# Thunderboard.net
KiCad netlist of a schematic drawn in EAGLE
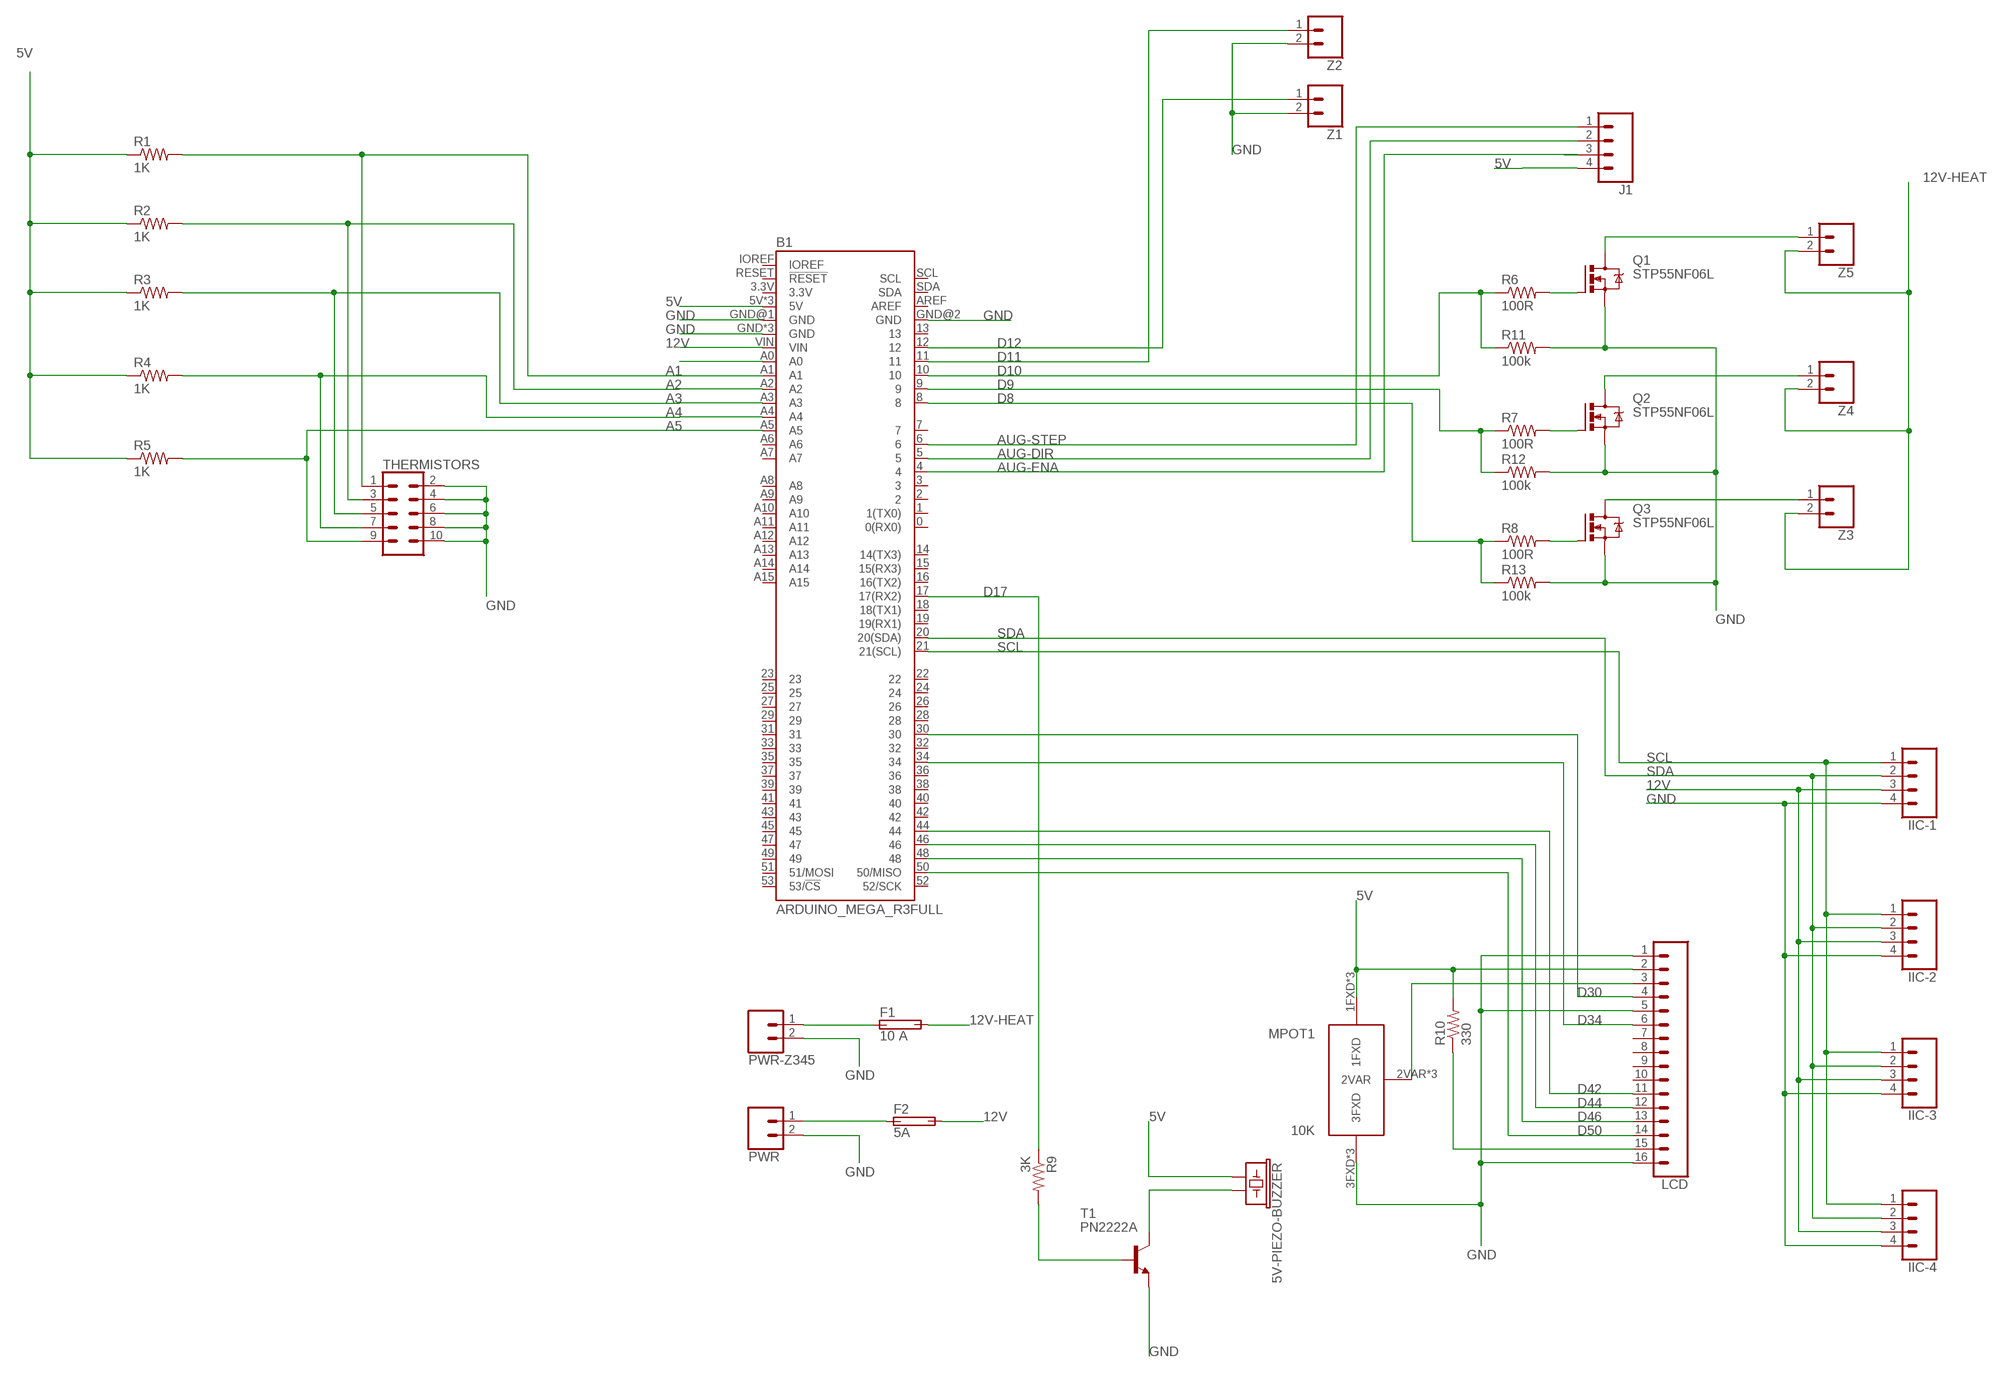
[diagram p0: schematic, sheet 1]

(export (version "E")
  (design (tool "Eeschema 10.0.6"))
  (components
    (comp (ref "5V-PIEZO-BUZZER")
      (value "BUZZER-PTH")
      (footprint "eagle-import:BUZZER-12MM")
      (libsource (lib "eagle-import") (part "BUZZER-PTH"))
    )
    (comp (ref "B1")
      (value "ARDUINO_MEGA_R3FULL")
      (footprint "eagle-import:ARDUINO_MEGA_NO_SILK")
      (libsource (lib "eagle-import") (part "ARDUINO_MEGA_R3FULL"))
    )
    (comp (ref "F1")
      (value "10 A")
      (footprint "eagle-import:MINI-BLADE")
      (libsource (lib "eagle-import") (part "BLADE-FUSE-HOLDER3557-15"))
    )
    (comp (ref "F2")
      (value "5A")
      (footprint "eagle-import:MINI-BLADE")
      (libsource (lib "eagle-import") (part "BLADE-FUSE-HOLDER3557-15"))
    )
    (comp (ref "IIC-1")
      (value "CONN_04")
      (footprint "eagle-import:1X04")
      (libsource (lib "eagle-import") (part "CONN_04"))
    )
    (comp (ref "IIC-2")
      (value "CONN_04")
      (footprint "eagle-import:1X04")
      (libsource (lib "eagle-import") (part "CONN_04"))
    )
    (comp (ref "IIC-3")
      (value "CONN_04")
      (footprint "eagle-import:1X04")
      (libsource (lib "eagle-import") (part "CONN_04"))
    )
    (comp (ref "IIC-4")
      (value "CONN_04")
      (footprint "eagle-import:1X04")
      (libsource (lib "eagle-import") (part "CONN_04"))
    )
    (comp (ref "J1")
      (value "CONN_04")
      (footprint "eagle-import:1X04")
      (libsource (lib "eagle-import") (part "CONN_04"))
    )
    (comp (ref "LCD")
      (value "CONN_16")
      (footprint "eagle-import:1X16")
      (libsource (lib "eagle-import") (part "CONN_16"))
    )
    (comp (ref "MPOT1")
      (value "10K")
      (footprint "eagle-import:POT-MULTI-PACKAGE")
      (libsource (lib "eagle-import") (part "POT-MULTI-PACKAGE"))
    )
    (comp (ref "PWR")
      (value "CONN_023.5MM")
      (footprint "eagle-import:SCREWTERMINAL-3.5MM-2")
      (libsource (lib "eagle-import") (part "CONN_023.5MM"))
    )
    (comp (ref "PWR-Z345")
      (value "CONN_023.5MM")
      (footprint "eagle-import:SCREWTERMINAL-3.5MM-2")
      (libsource (lib "eagle-import") (part "CONN_023.5MM"))
    )
    (comp (ref "Q1")
      (value "STP55NF06L")
      (footprint "eagle-import:TO-220")
      (libsource (lib "eagle-import") (part "STP55NF06L"))
    )
    (comp (ref "Q2")
      (value "STP55NF06L")
      (footprint "eagle-import:TO-220")
      (libsource (lib "eagle-import") (part "STP55NF06L"))
    )
    (comp (ref "Q3")
      (value "STP55NF06L")
      (footprint "eagle-import:TO-220")
      (libsource (lib "eagle-import") (part "STP55NF06L"))
    )
    (comp (ref "R1")
      (value "1K")
      (footprint "eagle-import:0207_7")
      (libsource (lib "eagle-import") (part "R-US_0207/7"))
    )
    (comp (ref "R2")
      (value "1K")
      (footprint "eagle-import:0207_7")
      (libsource (lib "eagle-import") (part "R-US_0207/7"))
    )
    (comp (ref "R3")
      (value "1K")
      (footprint "eagle-import:0207_7")
      (libsource (lib "eagle-import") (part "R-US_0207/7"))
    )
    (comp (ref "R4")
      (value "1K")
      (footprint "eagle-import:0207_7")
      (libsource (lib "eagle-import") (part "R-US_0207/7"))
    )
    (comp (ref "R5")
      (value "1K")
      (footprint "eagle-import:0207_7")
      (libsource (lib "eagle-import") (part "R-US_0207/7"))
    )
    (comp (ref "R6")
      (value "100R")
      (footprint "eagle-import:0207_7")
      (libsource (lib "eagle-import") (part "R-US_0207/7"))
    )
    (comp (ref "R7")
      (value "100R")
      (footprint "eagle-import:0207_7")
      (libsource (lib "eagle-import") (part "R-US_0207/7"))
    )
    (comp (ref "R8")
      (value "100R")
      (footprint "eagle-import:0207_7")
      (libsource (lib "eagle-import") (part "R-US_0207/7"))
    )
    (comp (ref "R9")
      (value "3K")
      (footprint "eagle-import:0207_7")
      (libsource (lib "eagle-import") (part "R-US_0207/7"))
    )
    (comp (ref "R10")
      (value "330")
      (footprint "eagle-import:0207_7")
      (libsource (lib "eagle-import") (part "R-US_0207/7"))
    )
    (comp (ref "R11")
      (value "100k")
      (footprint "eagle-import:0207_7")
      (libsource (lib "eagle-import") (part "R-US_0207/7"))
    )
    (comp (ref "R12")
      (value "100k")
      (footprint "eagle-import:0207_7")
      (libsource (lib "eagle-import") (part "R-US_0207/7"))
    )
    (comp (ref "R13")
      (value "100k")
      (footprint "eagle-import:0207_7")
      (libsource (lib "eagle-import") (part "R-US_0207/7"))
    )
    (comp (ref "T1")
      (value "PN2222A")
      (footprint "eagle-import:TO92-EBC")
      (libsource (lib "eagle-import") (part "-NPN-TO92-EBC"))
    )
    (comp (ref "THERMISTORS")
      (value "CONN_05X2NO_SILK")
      (footprint "eagle-import:2X5_NOSILK")
      (libsource (lib "eagle-import") (part "CONN_05X2NO_SILK"))
    )
    (comp (ref "Z1")
      (value "CONN_02")
      (footprint "eagle-import:1X02")
      (libsource (lib "eagle-import") (part "SparkFun-Connectors_513_CONN_02"))
    )
    (comp (ref "Z2")
      (value "CONN_02")
      (footprint "eagle-import:1X02")
      (libsource (lib "eagle-import") (part "SparkFun-Connectors_513_CONN_02"))
    )
    (comp (ref "Z3")
      (value "CONN_023.5MM")
      (footprint "eagle-import:SCREWTERMINAL-3.5MM-2")
      (libsource (lib "eagle-import") (part "CONN_023.5MM"))
    )
    (comp (ref "Z4")
      (value "CONN_023.5MM")
      (footprint "eagle-import:SCREWTERMINAL-3.5MM-2")
      (libsource (lib "eagle-import") (part "CONN_023.5MM"))
    )
    (comp (ref "Z5")
      (value "CONN_023.5MM")
      (footprint "eagle-import:SCREWTERMINAL-3.5MM-2")
      (libsource (lib "eagle-import") (part "CONN_023.5MM"))
    )
  )
  (nets
    (net (code "1") (name "/5V") (class "Default")
      (node (ref "5V-PIEZO-BUZZER") (pin "+") (pinfunction "1_+") (pintype "passive"))
      (node (ref "B1") (pin "5V") (pinfunction "5V_5V") (pintype "bidirectional"))
      (node (ref "B1") (pin "5V@1") (pinfunction "5V_5V@1") (pintype "bidirectional"))
      (node (ref "B1") (pin "5V@2") (pinfunction "5V_5V@2") (pintype "bidirectional"))
      (node (ref "J1") (pin "4") (pinfunction "4_4") (pintype "passive"))
      (node (ref "LCD") (pin "2") (pinfunction "2_2") (pintype "passive"))
      (node (ref "MPOT1") (pin "1FXD") (pinfunction "1FXD_1FXD") (pintype "bidirectional"))
      (node (ref "MPOT1") (pin "P$7") (pinfunction "1FXD_P$7") (pintype "bidirectional"))
      (node (ref "MPOT1") (pin "P$8") (pinfunction "1FXD_P$8") (pintype "bidirectional"))
      (node (ref "R1") (pin "1") (pinfunction "1_1") (pintype "passive"))
      (node (ref "R10") (pin "2") (pinfunction "2_2") (pintype "passive"))
      (node (ref "R2") (pin "1") (pinfunction "1_1") (pintype "passive"))
      (node (ref "R3") (pin "1") (pinfunction "1_1") (pintype "passive"))
      (node (ref "R4") (pin "1") (pinfunction "1_1") (pintype "passive"))
      (node (ref "R5") (pin "1") (pinfunction "1_1") (pintype "passive"))
    )
    (net (code "2") (name "/12V") (class "Default")
      (node (ref "B1") (pin "VIN") (pinfunction "VIN_VIN") (pintype "bidirectional"))
      (node (ref "F2") (pin "2A") (pinfunction "2_2A") (pintype "passive"))
      (node (ref "F2") (pin "2B") (pinfunction "2_2B") (pintype "passive"))
      (node (ref "IIC-1") (pin "3") (pinfunction "3_3") (pintype "passive"))
      (node (ref "IIC-2") (pin "3") (pinfunction "3_3") (pintype "passive"))
      (node (ref "IIC-3") (pin "3") (pinfunction "3_3") (pintype "passive"))
      (node (ref "IIC-4") (pin "3") (pinfunction "3_3") (pintype "passive"))
    )
    (net (code "3") (name "/12V-HEAT") (class "Default")
      (node (ref "F1") (pin "2A") (pinfunction "2_2A") (pintype "passive"))
      (node (ref "F1") (pin "2B") (pinfunction "2_2B") (pintype "passive"))
      (node (ref "Z3") (pin "2") (pinfunction "2_2") (pintype "passive"))
      (node (ref "Z4") (pin "2") (pinfunction "2_2") (pintype "passive"))
      (node (ref "Z5") (pin "2") (pinfunction "2_2") (pintype "passive"))
    )
    (net (code "4") (name "/A1") (class "Default")
      (node (ref "B1") (pin "A1") (pinfunction "A1_A1") (pintype "bidirectional"))
      (node (ref "R1") (pin "2") (pinfunction "2_2") (pintype "passive"))
      (node (ref "THERMISTORS") (pin "1") (pinfunction "1_1") (pintype "passive"))
    )
    (net (code "5") (name "/A2") (class "Default")
      (node (ref "B1") (pin "A2") (pinfunction "A2_A2") (pintype "bidirectional"))
      (node (ref "R2") (pin "2") (pinfunction "2_2") (pintype "passive"))
      (node (ref "THERMISTORS") (pin "3") (pinfunction "3_3") (pintype "passive"))
    )
    (net (code "6") (name "/A3") (class "Default")
      (node (ref "B1") (pin "A3") (pinfunction "A3_A3") (pintype "bidirectional"))
      (node (ref "R3") (pin "2") (pinfunction "2_2") (pintype "passive"))
      (node (ref "THERMISTORS") (pin "5") (pinfunction "5_5") (pintype "passive"))
    )
    (net (code "7") (name "/A4") (class "Default")
      (node (ref "B1") (pin "A4") (pinfunction "A4_A4") (pintype "bidirectional"))
      (node (ref "R4") (pin "2") (pinfunction "2_2") (pintype "passive"))
      (node (ref "THERMISTORS") (pin "7") (pinfunction "7_7") (pintype "passive"))
    )
    (net (code "8") (name "/A5") (class "Default")
      (node (ref "B1") (pin "A5") (pinfunction "A5_A5") (pintype "bidirectional"))
      (node (ref "R5") (pin "2") (pinfunction "2_2") (pintype "passive"))
      (node (ref "THERMISTORS") (pin "9") (pinfunction "9_9") (pintype "passive"))
    )
    (net (code "9") (name "/AUG-DIR") (class "Default")
      (node (ref "B1") (pin "5") (pinfunction "5_5") (pintype "bidirectional"))
      (node (ref "J1") (pin "2") (pinfunction "2_2") (pintype "passive"))
    )
    (net (code "10") (name "/AUG-ENA") (class "Default")
      (node (ref "B1") (pin "4") (pinfunction "4_4") (pintype "bidirectional"))
      (node (ref "J1") (pin "3") (pinfunction "3_3") (pintype "passive"))
    )
    (net (code "11") (name "/AUG-STEP") (class "Default")
      (node (ref "B1") (pin "6") (pinfunction "6_6") (pintype "bidirectional"))
      (node (ref "J1") (pin "1") (pinfunction "1_1") (pintype "passive"))
    )
    (net (code "12") (name "/D8") (class "Default")
      (node (ref "B1") (pin "8") (pinfunction "8_8") (pintype "bidirectional"))
      (node (ref "R13") (pin "1") (pinfunction "1_1") (pintype "passive"))
      (node (ref "R8") (pin "1") (pinfunction "1_1") (pintype "passive"))
    )
    (net (code "13") (name "/D9") (class "Default")
      (node (ref "B1") (pin "9") (pinfunction "9_9") (pintype "bidirectional"))
      (node (ref "R12") (pin "1") (pinfunction "1_1") (pintype "passive"))
      (node (ref "R7") (pin "1") (pinfunction "1_1") (pintype "passive"))
    )
    (net (code "14") (name "/D10") (class "Default")
      (node (ref "B1") (pin "10") (pinfunction "10_10") (pintype "bidirectional"))
      (node (ref "R11") (pin "1") (pinfunction "1_1") (pintype "passive"))
      (node (ref "R6") (pin "1") (pinfunction "1_1") (pintype "passive"))
    )
    (net (code "15") (name "/D11") (class "Default")
      (node (ref "B1") (pin "11") (pinfunction "11_11") (pintype "bidirectional"))
      (node (ref "Z2") (pin "1") (pinfunction "1_1") (pintype "passive"))
    )
    (net (code "16") (name "/D12") (class "Default")
      (node (ref "B1") (pin "12") (pinfunction "12_12") (pintype "bidirectional"))
      (node (ref "Z1") (pin "1") (pinfunction "1_1") (pintype "passive"))
    )
    (net (code "17") (name "/D17") (class "Default")
      (node (ref "B1") (pin "17") (pinfunction "17(RX2)_17") (pintype "bidirectional"))
      (node (ref "R9") (pin "1") (pinfunction "1_1") (pintype "passive"))
    )
    (net (code "18") (name "/D30") (class "Default")
      (node (ref "B1") (pin "30") (pinfunction "30_30") (pintype "bidirectional"))
      (node (ref "LCD") (pin "4") (pinfunction "4_4") (pintype "passive"))
    )
    (net (code "19") (name "/D34") (class "Default")
      (node (ref "B1") (pin "34") (pinfunction "34_34") (pintype "bidirectional"))
      (node (ref "LCD") (pin "6") (pinfunction "6_6") (pintype "passive"))
    )
    (net (code "20") (name "/D42") (class "Default")
      (node (ref "B1") (pin "44") (pinfunction "44_44") (pintype "bidirectional"))
      (node (ref "LCD") (pin "11") (pinfunction "11_11") (pintype "passive"))
    )
    (net (code "21") (name "/D44") (class "Default")
      (node (ref "B1") (pin "46") (pinfunction "46_46") (pintype "bidirectional"))
      (node (ref "LCD") (pin "12") (pinfunction "12_12") (pintype "passive"))
    )
    (net (code "22") (name "/D46") (class "Default")
      (node (ref "B1") (pin "48") (pinfunction "48_48") (pintype "bidirectional"))
      (node (ref "LCD") (pin "13") (pinfunction "13_13") (pintype "passive"))
    )
    (net (code "23") (name "/D50") (class "Default")
      (node (ref "B1") (pin "50") (pinfunction "50/MISO_50") (pintype "bidirectional"))
      (node (ref "LCD") (pin "14") (pinfunction "14_14") (pintype "passive"))
    )
    (net (code "24") (name "/GND") (class "Default")
      (node (ref "B1") (pin "GND") (pinfunction "GND_GND") (pintype "bidirectional"))
      (node (ref "B1") (pin "GND@1") (pinfunction "GND_GND@1") (pintype "bidirectional"))
      (node (ref "B1") (pin "GND@2") (pinfunction "GND_GND@2") (pintype "bidirectional"))
      (node (ref "B1") (pin "GND@3") (pinfunction "GND_GND@3") (pintype "bidirectional"))
      (node (ref "B1") (pin "GND@4") (pinfunction "GND_GND@4") (pintype "bidirectional"))
      (node (ref "IIC-1") (pin "4") (pinfunction "4_4") (pintype "passive"))
      (node (ref "IIC-2") (pin "4") (pinfunction "4_4") (pintype "passive"))
      (node (ref "IIC-3") (pin "4") (pinfunction "4_4") (pintype "passive"))
      (node (ref "IIC-4") (pin "4") (pinfunction "4_4") (pintype "passive"))
      (node (ref "LCD") (pin "1") (pinfunction "1_1") (pintype "passive"))
      (node (ref "LCD") (pin "16") (pinfunction "16_16") (pintype "passive"))
      (node (ref "LCD") (pin "5") (pinfunction "5_5") (pintype "passive"))
      (node (ref "MPOT1") (pin "3FXD") (pinfunction "3FXD_3FXD") (pintype "bidirectional"))
      (node (ref "MPOT1") (pin "P$4") (pinfunction "3FXD_P$4") (pintype "bidirectional"))
      (node (ref "MPOT1") (pin "P$5") (pinfunction "3FXD_P$5") (pintype "bidirectional"))
      (node (ref "PWR") (pin "2") (pinfunction "2_2") (pintype "passive"))
      (node (ref "PWR-Z345") (pin "2") (pinfunction "2_2") (pintype "passive"))
      (node (ref "Q1") (pin "S") (pinfunction "S_S") (pintype "passive"))
      (node (ref "Q2") (pin "S") (pinfunction "S_S") (pintype "passive"))
      (node (ref "Q3") (pin "S") (pinfunction "S_S") (pintype "passive"))
      (node (ref "R11") (pin "2") (pinfunction "2_2") (pintype "passive"))
      (node (ref "R12") (pin "2") (pinfunction "2_2") (pintype "passive"))
      (node (ref "R13") (pin "2") (pinfunction "2_2") (pintype "passive"))
      (node (ref "T1") (pin "E") (pinfunction "E_E") (pintype "passive"))
      (node (ref "THERMISTORS") (pin "10") (pinfunction "10_10") (pintype "passive"))
      (node (ref "THERMISTORS") (pin "2") (pinfunction "2_2") (pintype "passive"))
      (node (ref "THERMISTORS") (pin "4") (pinfunction "4_4") (pintype "passive"))
      (node (ref "THERMISTORS") (pin "6") (pinfunction "6_6") (pintype "passive"))
      (node (ref "THERMISTORS") (pin "8") (pinfunction "8_8") (pintype "passive"))
      (node (ref "Z1") (pin "2") (pinfunction "2_2") (pintype "passive"))
      (node (ref "Z2") (pin "2") (pinfunction "2_2") (pintype "passive"))
    )
    (net (code "25") (name "/SCL") (class "Default")
      (node (ref "B1") (pin "21") (pinfunction "21(SCL)_21") (pintype "bidirectional"))
      (node (ref "IIC-1") (pin "1") (pinfunction "1_1") (pintype "passive"))
      (node (ref "IIC-2") (pin "1") (pinfunction "1_1") (pintype "passive"))
      (node (ref "IIC-3") (pin "1") (pinfunction "1_1") (pintype "passive"))
      (node (ref "IIC-4") (pin "1") (pinfunction "1_1") (pintype "passive"))
    )
    (net (code "26") (name "/SDA") (class "Default")
      (node (ref "B1") (pin "20") (pinfunction "20(SDA)_20") (pintype "bidirectional"))
      (node (ref "IIC-1") (pin "2") (pinfunction "2_2") (pintype "passive"))
      (node (ref "IIC-2") (pin "2") (pinfunction "2_2") (pintype "passive"))
      (node (ref "IIC-3") (pin "2") (pinfunction "2_2") (pintype "passive"))
      (node (ref "IIC-4") (pin "2") (pinfunction "2_2") (pintype "passive"))
    )
    (net (code "27") (name "Net-(5V-PIEZO-BUZZER-2)") (class "Default")
      (node (ref "5V-PIEZO-BUZZER") (pin "-") (pinfunction "2_-") (pintype "passive"))
      (node (ref "T1") (pin "C") (pinfunction "C_C") (pintype "passive"))
    )
    (net (code "28") (name "Net-(F1-1-Pad1A)") (class "Default")
      (node (ref "F1") (pin "1A") (pinfunction "1_1A") (pintype "passive"))
      (node (ref "F1") (pin "1B") (pinfunction "1_1B") (pintype "passive"))
      (node (ref "PWR-Z345") (pin "1") (pinfunction "1_1") (pintype "passive"))
    )
    (net (code "29") (name "Net-(F2-1-Pad1A)") (class "Default")
      (node (ref "F2") (pin "1A") (pinfunction "1_1A") (pintype "passive"))
      (node (ref "F2") (pin "1B") (pinfunction "1_1B") (pintype "passive"))
      (node (ref "PWR") (pin "1") (pinfunction "1_1") (pintype "passive"))
    )
    (net (code "30") (name "Net-(LCD-Pad3)") (class "Default")
      (node (ref "LCD") (pin "3") (pinfunction "3_3") (pintype "passive"))
      (node (ref "MPOT1") (pin "2VAR") (pinfunction "2VAR_2VAR") (pintype "bidirectional"))
      (node (ref "MPOT1") (pin "P$1") (pinfunction "2VAR_P$1") (pintype "bidirectional"))
      (node (ref "MPOT1") (pin "P$3") (pinfunction "2VAR_P$3") (pintype "bidirectional"))
    )
    (net (code "31") (name "Net-(LCD-Pad15)") (class "Default")
      (node (ref "LCD") (pin "15") (pinfunction "15_15") (pintype "passive"))
      (node (ref "R10") (pin "1") (pinfunction "1_1") (pintype "passive"))
    )
    (net (code "32") (name "Net-(Q1-PadD)") (class "Default")
      (node (ref "Q1") (pin "D") (pinfunction "D_D") (pintype "passive"))
      (node (ref "Z5") (pin "1") (pinfunction "1_1") (pintype "passive"))
    )
    (net (code "33") (name "Net-(Q1-PadG)") (class "Default")
      (node (ref "Q1") (pin "G") (pinfunction "G_G") (pintype "passive"))
      (node (ref "R6") (pin "2") (pinfunction "2_2") (pintype "passive"))
    )
    (net (code "34") (name "Net-(Q2-PadD)") (class "Default")
      (node (ref "Q2") (pin "D") (pinfunction "D_D") (pintype "passive"))
      (node (ref "Z4") (pin "1") (pinfunction "1_1") (pintype "passive"))
    )
    (net (code "35") (name "Net-(Q2-PadG)") (class "Default")
      (node (ref "Q2") (pin "G") (pinfunction "G_G") (pintype "passive"))
      (node (ref "R7") (pin "2") (pinfunction "2_2") (pintype "passive"))
    )
    (net (code "36") (name "Net-(Q3-PadD)") (class "Default")
      (node (ref "Q3") (pin "D") (pinfunction "D_D") (pintype "passive"))
      (node (ref "Z3") (pin "1") (pinfunction "1_1") (pintype "passive"))
    )
    (net (code "37") (name "Net-(Q3-PadG)") (class "Default")
      (node (ref "Q3") (pin "G") (pinfunction "G_G") (pintype "passive"))
      (node (ref "R8") (pin "2") (pinfunction "2_2") (pintype "passive"))
    )
    (net (code "38") (name "Net-(R9-Pad2)") (class "Default")
      (node (ref "R9") (pin "2") (pinfunction "2_2") (pintype "passive"))
      (node (ref "T1") (pin "B") (pinfunction "B_B") (pintype "passive"))
    )
    (net (code "39") (name "unconnected-(B1-0(RX0)-Pad0)") (class "Default")
      (node (ref "B1") (pin "0") (pinfunction "0(RX0)_0") (pintype "bidirectional"))
    )
    (net (code "40") (name "unconnected-(B1-1(TX0)-Pad1)") (class "Default")
      (node (ref "B1") (pin "1") (pinfunction "1(TX0)_1") (pintype "bidirectional"))
    )
    (net (code "41") (name "unconnected-(B1-14(TX3)-Pad14)") (class "Default")
      (node (ref "B1") (pin "14") (pinfunction "14(TX3)_14") (pintype "bidirectional"))
    )
    (net (code "42") (name "unconnected-(B1-15(RX3)-Pad15)") (class "Default")
      (node (ref "B1") (pin "15") (pinfunction "15(RX3)_15") (pintype "bidirectional"))
    )
    (net (code "43") (name "unconnected-(B1-16(TX2)-Pad16)") (class "Default")
      (node (ref "B1") (pin "16") (pinfunction "16(TX2)_16") (pintype "bidirectional"))
    )
    (net (code "44") (name "unconnected-(B1-18(TX1)-Pad18)") (class "Default")
      (node (ref "B1") (pin "18") (pinfunction "18(TX1)_18") (pintype "bidirectional"))
    )
    (net (code "45") (name "unconnected-(B1-19(RX1)-Pad19)") (class "Default")
      (node (ref "B1") (pin "19") (pinfunction "19(RX1)_19") (pintype "bidirectional"))
    )
    (net (code "46") (name "unconnected-(B1-51{slash}MOSI-Pad51)") (class "Default")
      (node (ref "B1") (pin "51") (pinfunction "51/MOSI_51") (pintype "bidirectional"))
    )
    (net (code "47") (name "unconnected-(B1-52{slash}SCK-Pad52)") (class "Default")
      (node (ref "B1") (pin "52") (pinfunction "52/SCK_52") (pintype "bidirectional"))
    )
    (net (code "48") (name "unconnected-(B1-53{slash}~{CS}-Pad53)") (class "Default")
      (node (ref "B1") (pin "53") (pinfunction "53/~{CS}_53") (pintype "bidirectional"))
    )
    (net (code "49") (name "unconnected-(B1-Pad2)") (class "Default")
      (node (ref "B1") (pin "2") (pinfunction "2_2") (pintype "bidirectional"))
    )
    (net (code "50") (name "unconnected-(B1-Pad3)") (class "Default")
      (node (ref "B1") (pin "3") (pinfunction "3_3") (pintype "bidirectional"))
    )
    (net (code "51") (name "unconnected-(B1-Pad3.3V)") (class "Default")
      (node (ref "B1") (pin "3.3V") (pinfunction "3.3V_3.3V") (pintype "bidirectional"))
    )
    (net (code "52") (name "unconnected-(B1-Pad7)") (class "Default")
      (node (ref "B1") (pin "7") (pinfunction "7_7") (pintype "bidirectional"))
    )
    (net (code "53") (name "unconnected-(B1-Pad13)") (class "Default")
      (node (ref "B1") (pin "13") (pinfunction "13_13") (pintype "bidirectional"))
    )
    (net (code "54") (name "unconnected-(B1-Pad22)") (class "Default")
      (node (ref "B1") (pin "22") (pinfunction "22_22") (pintype "bidirectional"))
    )
    (net (code "55") (name "unconnected-(B1-Pad23)") (class "Default")
      (node (ref "B1") (pin "23") (pinfunction "23_23") (pintype "bidirectional"))
    )
    (net (code "56") (name "unconnected-(B1-Pad24)") (class "Default")
      (node (ref "B1") (pin "24") (pinfunction "24_24") (pintype "bidirectional"))
    )
    (net (code "57") (name "unconnected-(B1-Pad25)") (class "Default")
      (node (ref "B1") (pin "25") (pinfunction "25_25") (pintype "bidirectional"))
    )
    (net (code "58") (name "unconnected-(B1-Pad26)") (class "Default")
      (node (ref "B1") (pin "26") (pinfunction "26_26") (pintype "bidirectional"))
    )
    (net (code "59") (name "unconnected-(B1-Pad27)") (class "Default")
      (node (ref "B1") (pin "27") (pinfunction "27_27") (pintype "bidirectional"))
    )
    (net (code "60") (name "unconnected-(B1-Pad28)") (class "Default")
      (node (ref "B1") (pin "28") (pinfunction "28_28") (pintype "bidirectional"))
    )
    (net (code "61") (name "unconnected-(B1-Pad29)") (class "Default")
      (node (ref "B1") (pin "29") (pinfunction "29_29") (pintype "bidirectional"))
    )
    (net (code "62") (name "unconnected-(B1-Pad31)") (class "Default")
      (node (ref "B1") (pin "31") (pinfunction "31_31") (pintype "bidirectional"))
    )
    (net (code "63") (name "unconnected-(B1-Pad32)") (class "Default")
      (node (ref "B1") (pin "32") (pinfunction "32_32") (pintype "bidirectional"))
    )
    (net (code "64") (name "unconnected-(B1-Pad33)") (class "Default")
      (node (ref "B1") (pin "33") (pinfunction "33_33") (pintype "bidirectional"))
    )
    (net (code "65") (name "unconnected-(B1-Pad35)") (class "Default")
      (node (ref "B1") (pin "35") (pinfunction "35_35") (pintype "bidirectional"))
    )
    (net (code "66") (name "unconnected-(B1-Pad36)") (class "Default")
      (node (ref "B1") (pin "36") (pinfunction "36_36") (pintype "bidirectional"))
    )
    (net (code "67") (name "unconnected-(B1-Pad37)") (class "Default")
      (node (ref "B1") (pin "37") (pinfunction "37_37") (pintype "bidirectional"))
    )
    (net (code "68") (name "unconnected-(B1-Pad38)") (class "Default")
      (node (ref "B1") (pin "38") (pinfunction "38_38") (pintype "bidirectional"))
    )
    (net (code "69") (name "unconnected-(B1-Pad39)") (class "Default")
      (node (ref "B1") (pin "39") (pinfunction "39_39") (pintype "bidirectional"))
    )
    (net (code "70") (name "unconnected-(B1-Pad40)") (class "Default")
      (node (ref "B1") (pin "40") (pinfunction "40_40") (pintype "bidirectional"))
    )
    (net (code "71") (name "unconnected-(B1-Pad41)") (class "Default")
      (node (ref "B1") (pin "41") (pinfunction "41_41") (pintype "bidirectional"))
    )
    (net (code "72") (name "unconnected-(B1-Pad42)") (class "Default")
      (node (ref "B1") (pin "42") (pinfunction "42_42") (pintype "bidirectional"))
    )
    (net (code "73") (name "unconnected-(B1-Pad43)") (class "Default")
      (node (ref "B1") (pin "43") (pinfunction "43_43") (pintype "bidirectional"))
    )
    (net (code "74") (name "unconnected-(B1-Pad45)") (class "Default")
      (node (ref "B1") (pin "45") (pinfunction "45_45") (pintype "bidirectional"))
    )
    (net (code "75") (name "unconnected-(B1-Pad47)") (class "Default")
      (node (ref "B1") (pin "47") (pinfunction "47_47") (pintype "bidirectional"))
    )
    (net (code "76") (name "unconnected-(B1-Pad49)") (class "Default")
      (node (ref "B1") (pin "49") (pinfunction "49_49") (pintype "bidirectional"))
    )
    (net (code "77") (name "unconnected-(B1-PadA0)") (class "Default")
      (node (ref "B1") (pin "A0") (pinfunction "A0_A0") (pintype "bidirectional"))
    )
    (net (code "78") (name "unconnected-(B1-PadA6)") (class "Default")
      (node (ref "B1") (pin "A6") (pinfunction "A6_A6") (pintype "bidirectional"))
    )
    (net (code "79") (name "unconnected-(B1-PadA7)") (class "Default")
      (node (ref "B1") (pin "A7") (pinfunction "A7_A7") (pintype "bidirectional"))
    )
    (net (code "80") (name "unconnected-(B1-PadA8)") (class "Default")
      (node (ref "B1") (pin "A8") (pinfunction "A8_A8") (pintype "bidirectional"))
    )
    (net (code "81") (name "unconnected-(B1-PadA9)") (class "Default")
      (node (ref "B1") (pin "A9") (pinfunction "A9_A9") (pintype "bidirectional"))
    )
    (net (code "82") (name "unconnected-(B1-PadA10)") (class "Default")
      (node (ref "B1") (pin "A10") (pinfunction "A10_A10") (pintype "bidirectional"))
    )
    (net (code "83") (name "unconnected-(B1-PadA11)") (class "Default")
      (node (ref "B1") (pin "A11") (pinfunction "A11_A11") (pintype "bidirectional"))
    )
    (net (code "84") (name "unconnected-(B1-PadA12)") (class "Default")
      (node (ref "B1") (pin "A12") (pinfunction "A12_A12") (pintype "bidirectional"))
    )
    (net (code "85") (name "unconnected-(B1-PadA13)") (class "Default")
      (node (ref "B1") (pin "A13") (pinfunction "A13_A13") (pintype "bidirectional"))
    )
    (net (code "86") (name "unconnected-(B1-PadA14)") (class "Default")
      (node (ref "B1") (pin "A14") (pinfunction "A14_A14") (pintype "bidirectional"))
    )
    (net (code "87") (name "unconnected-(B1-PadA15)") (class "Default")
      (node (ref "B1") (pin "A15") (pinfunction "A15_A15") (pintype "bidirectional"))
    )
    (net (code "88") (name "unconnected-(B1-PadAREF)") (class "Default")
      (node (ref "B1") (pin "AREF") (pinfunction "AREF_AREF") (pintype "bidirectional"))
    )
    (net (code "89") (name "unconnected-(B1-PadIOREF)") (class "Default")
      (node (ref "B1") (pin "IOREF") (pinfunction "IOREF_IOREF") (pintype "bidirectional"))
    )
    (net (code "90") (name "unconnected-(B1-PadSCL)") (class "Default")
      (node (ref "B1") (pin "SCL") (pinfunction "SCL_SCL") (pintype "bidirectional"))
    )
    (net (code "91") (name "unconnected-(B1-PadSDA)") (class "Default")
      (node (ref "B1") (pin "SDA") (pinfunction "SDA_SDA") (pintype "bidirectional"))
    )
    (net (code "92") (name "unconnected-(B1-~{RESET}-PadRESET)") (class "Default")
      (node (ref "B1") (pin "RESET") (pinfunction "~{RESET}_RESET") (pintype "bidirectional"))
    )
    (net (code "93") (name "unconnected-(LCD-Pad7)") (class "Default")
      (node (ref "LCD") (pin "7") (pinfunction "7_7") (pintype "passive"))
    )
    (net (code "94") (name "unconnected-(LCD-Pad8)") (class "Default")
      (node (ref "LCD") (pin "8") (pinfunction "8_8") (pintype "passive"))
    )
    (net (code "95") (name "unconnected-(LCD-Pad9)") (class "Default")
      (node (ref "LCD") (pin "9") (pinfunction "9_9") (pintype "passive"))
    )
    (net (code "96") (name "unconnected-(LCD-Pad10)") (class "Default")
      (node (ref "LCD") (pin "10") (pinfunction "10_10") (pintype "passive"))
    )
  )
)
